# 05_LEDs.net
KiCad netlist of a schematic drawn in Altium Designer
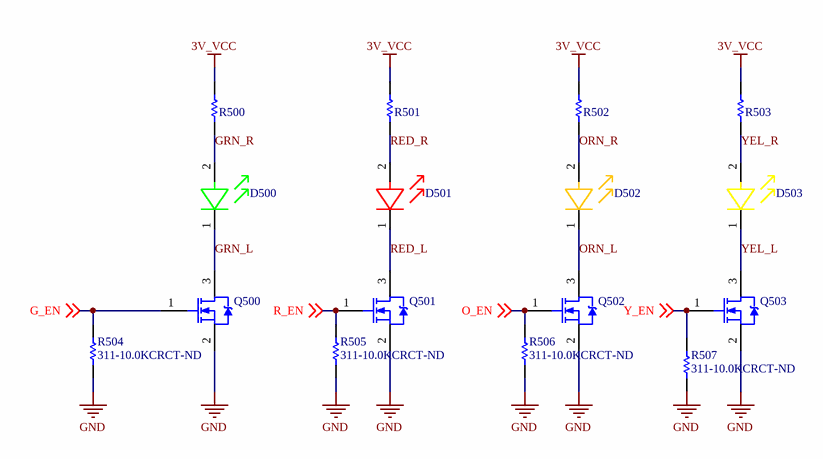
[diagram p0: 05_LEDs.SchDoc]

(export (version "E")
  (design (tool "Eeschema 10.0.6"))
  (components
    (comp (ref "D500")
      (value "LED_GREEN_0805.1")
      (footprint "LED_GRN_0805")
      (description "LED GREEN CLEAR THIN 0805 SMD")
      (fields
        (field (name "MANUFACTURER") "Vishay / Lite-On")
        (field (name "MANUFACTURER PART NUMBER") "LTST-C171KGKT")
      )
      (libsource (lib "ece315") (part "LED_GREEN_0805.1"))
    )
    (comp (ref "D501")
      (value "LED_RED_0805.1")
      (footprint "LED_RED_0805")
      (description "LED SUPER RED CLR THIN 0805 SMD")
      (fields
        (field (name "MANUFACTURER") "Vishay / Lite-On")
        (field (name "MANUFACTURER PART NUMBER") "LTST-C171KRKT")
      )
      (libsource (lib "ece315") (part "LED_RED_0805.1"))
    )
    (comp (ref "D502")
      (value "LED_ORANGE.0805.1")
      (footprint "LED_ORG_0805")
      (description "LED ORANGE DIFFUSED 0805 SMD")
      (fields (field (name "MANUFACTURER") "Rohm") (field (name "MANUFACTURER PART NUMBER") "SML-210DTT86"))
      (libsource (lib "ece315") (part "LED_ORANGE.0805.1"))
    )
    (comp (ref "D503")
      (value "LED_YELLOW_0805.1")
      (footprint "LED_YEL_0805")
      (description "LED YELLOW CLEAR THIN 0805 SMD")
      (fields
        (field (name "MANUFACTURER") "Vishay / Lite-On")
        (field (name "MANUFACTURER PART NUMBER") "LTST-C171KSKT")
      )
      (libsource (lib "ece315") (part "LED_YELLOW_0805.1"))
    )
    (comp (ref "Q500")
      (value "IC_NMOS_DMN2020LSN")
      (footprint "SOT23")
      (fields (field (name "MANUFACTURER") "Diodes") (field (name "MANUFACTURER PART NUMBER") "DMN2020LSN-7"))
      (libsource (lib "ece315") (part "IC_NMOS_DMN2020LSN"))
    )
    (comp (ref "Q501")
      (value "IC_NMOS_DMN2020LSN")
      (footprint "SOT23")
      (fields (field (name "MANUFACTURER") "Diodes") (field (name "MANUFACTURER PART NUMBER") "DMN2020LSN-7"))
      (libsource (lib "ece315") (part "IC_NMOS_DMN2020LSN"))
    )
    (comp (ref "Q502")
      (value "IC_NMOS_DMN2020LSN")
      (footprint "SOT23")
      (fields (field (name "MANUFACTURER") "Diodes") (field (name "MANUFACTURER PART NUMBER") "DMN2020LSN-7"))
      (libsource (lib "ece315") (part "IC_NMOS_DMN2020LSN"))
    )
    (comp (ref "Q503")
      (value "IC_NMOS_DMN2020LSN")
      (footprint "SOT23")
      (fields (field (name "MANUFACTURER") "Diodes") (field (name "MANUFACTURER PART NUMBER") "DMN2020LSN-7"))
      (libsource (lib "ece315") (part "IC_NMOS_DMN2020LSN"))
    )
    (comp (ref "R500")
      (value "330")
      (footprint "RES_0805")
      (description "RES SMD 330 OHM 1% 1/8W 0805")
      (fields
        (field (name "MANUFACTURER") "Yageo")
        (field (name "MANUFACTURER PART NUMBER") "RC0805FR-07330RL")
      )
      (libsource (lib "ece315") (part "RES_0805_R_330.00"))
    )
    (comp (ref "R501")
      (value "330")
      (footprint "RES_0805")
      (description "RES SMD 330 OHM 1% 1/8W 0805")
      (fields
        (field (name "MANUFACTURER") "Yageo")
        (field (name "MANUFACTURER PART NUMBER") "RC0805FR-07330RL")
      )
      (libsource (lib "ece315") (part "RES_0805_R_330.00"))
    )
    (comp (ref "R502")
      (value "330")
      (footprint "RES_0805")
      (description "RES SMD 330 OHM 1% 1/8W 0805")
      (fields
        (field (name "MANUFACTURER") "Yageo")
        (field (name "MANUFACTURER PART NUMBER") "RC0805FR-07330RL")
      )
      (libsource (lib "ece315") (part "RES_0805_R_330.00"))
    )
    (comp (ref "R503")
      (value "330")
      (footprint "RES_0805")
      (description "RES SMD 330 OHM 1% 1/8W 0805")
      (fields
        (field (name "MANUFACTURER") "Yageo")
        (field (name "MANUFACTURER PART NUMBER") "RC0805FR-07330RL")
      )
      (libsource (lib "ece315") (part "RES_0805_R_330.00"))
    )
    (comp (ref "R504")
      (value "10K")
      (footprint "RES_0805")
      (description "RES SMD 10K OHM 1% 1/8W 0805")
      (fields
        (field (name "MANUFACTURER") "Yageo")
        (field (name "MANUFACTURER PART NUMBER") "RC0805FR-0710KL")
        (field (name "SUPPLIER PART NUMBER 1") "311-10.0KCRCT-ND")
      )
      (libsource (lib "ece315") (part "RES_0805_K_010.00"))
    )
    (comp (ref "R505")
      (value "10K")
      (footprint "RES_0805")
      (description "RES SMD 10K OHM 1% 1/8W 0805")
      (fields
        (field (name "MANUFACTURER") "Yageo")
        (field (name "MANUFACTURER PART NUMBER") "RC0805FR-0710KL")
        (field (name "SUPPLIER PART NUMBER 1") "311-10.0KCRCT-ND")
      )
      (libsource (lib "ece315") (part "RES_0805_K_010.00"))
    )
    (comp (ref "R506")
      (value "10K")
      (footprint "RES_0805")
      (description "RES SMD 10K OHM 1% 1/8W 0805")
      (fields
        (field (name "MANUFACTURER") "Yageo")
        (field (name "MANUFACTURER PART NUMBER") "RC0805FR-0710KL")
        (field (name "SUPPLIER PART NUMBER 1") "311-10.0KCRCT-ND")
      )
      (libsource (lib "ece315") (part "RES_0805_K_010.00"))
    )
    (comp (ref "R507")
      (value "10K")
      (footprint "RES_0805")
      (description "RES SMD 10K OHM 1% 1/8W 0805")
      (fields
        (field (name "MANUFACTURER") "Yageo")
        (field (name "MANUFACTURER PART NUMBER") "RC0805FR-0710KL")
        (field (name "SUPPLIER PART NUMBER 1") "311-10.0KCRCT-ND")
      )
      (libsource (lib "ece315") (part "RES_0805_K_010.00"))
    )
  )
  (nets
    (net (code "1") (name "/GRN_L") (class "Default")
      (node (ref "D500") (pin "1") (pinfunction "Cathode_1") (pintype "passive"))
      (node (ref "Q500") (pin "3") (pinfunction "3_3") (pintype "passive"))
    )
    (net (code "2") (name "/GRN_R") (class "Default")
      (node (ref "D500") (pin "2") (pinfunction "Anode_2") (pintype "passive"))
      (node (ref "R500") (pin "1") (pinfunction "1_1") (pintype "passive"))
    )
    (net (code "3") (name "/ORN_L") (class "Default")
      (node (ref "D502") (pin "1") (pinfunction "Cathode_1") (pintype "passive"))
      (node (ref "Q502") (pin "3") (pinfunction "3_3") (pintype "passive"))
    )
    (net (code "4") (name "/ORN_R") (class "Default")
      (node (ref "D502") (pin "2") (pinfunction "Anode_2") (pintype "passive"))
      (node (ref "R502") (pin "1") (pinfunction "1_1") (pintype "passive"))
    )
    (net (code "5") (name "/RED_L") (class "Default")
      (node (ref "D501") (pin "1") (pinfunction "Cathode_1") (pintype "passive"))
      (node (ref "Q501") (pin "3") (pinfunction "3_3") (pintype "passive"))
    )
    (net (code "6") (name "/RED_R") (class "Default")
      (node (ref "D501") (pin "2") (pinfunction "Anode_2") (pintype "passive"))
      (node (ref "R501") (pin "1") (pinfunction "1_1") (pintype "passive"))
    )
    (net (code "7") (name "/YEL_L") (class "Default")
      (node (ref "D503") (pin "1") (pinfunction "Cathode_1") (pintype "passive"))
      (node (ref "Q503") (pin "3") (pinfunction "3_3") (pintype "passive"))
    )
    (net (code "8") (name "/YEL_R") (class "Default")
      (node (ref "D503") (pin "2") (pinfunction "Anode_2") (pintype "passive"))
      (node (ref "R503") (pin "1") (pinfunction "1_1") (pintype "passive"))
    )
    (net (code "9") (name "3V_VCC") (class "Default")
      (node (ref "R500") (pin "2") (pinfunction "2_2") (pintype "passive"))
      (node (ref "R501") (pin "2") (pinfunction "2_2") (pintype "passive"))
      (node (ref "R502") (pin "2") (pinfunction "2_2") (pintype "passive"))
      (node (ref "R503") (pin "2") (pinfunction "2_2") (pintype "passive"))
    )
    (net (code "10") (name "GND") (class "Default")
      (node (ref "Q500") (pin "2") (pinfunction "2_2") (pintype "passive"))
      (node (ref "Q501") (pin "2") (pinfunction "2_2") (pintype "passive"))
      (node (ref "Q502") (pin "2") (pinfunction "2_2") (pintype "passive"))
      (node (ref "Q503") (pin "2") (pinfunction "2_2") (pintype "passive"))
      (node (ref "R504") (pin "1") (pinfunction "1_1") (pintype "passive"))
      (node (ref "R505") (pin "1") (pinfunction "1_1") (pintype "passive"))
      (node (ref "R506") (pin "1") (pinfunction "1_1") (pintype "passive"))
      (node (ref "R507") (pin "1") (pinfunction "1_1") (pintype "passive"))
    )
    (net (code "11") (name "G_EN") (class "Default")
      (node (ref "Q500") (pin "1") (pinfunction "1_1") (pintype "passive"))
      (node (ref "R504") (pin "2") (pinfunction "2_2") (pintype "passive"))
    )
    (net (code "12") (name "O_EN") (class "Default")
      (node (ref "Q502") (pin "1") (pinfunction "1_1") (pintype "passive"))
      (node (ref "R506") (pin "2") (pinfunction "2_2") (pintype "passive"))
    )
    (net (code "13") (name "R_EN") (class "Default")
      (node (ref "Q501") (pin "1") (pinfunction "1_1") (pintype "passive"))
      (node (ref "R505") (pin "2") (pinfunction "2_2") (pintype "passive"))
    )
    (net (code "14") (name "Y_EN") (class "Default")
      (node (ref "Q503") (pin "1") (pinfunction "1_1") (pintype "passive"))
      (node (ref "R507") (pin "2") (pinfunction "2_2") (pintype "passive"))
    )
  )
)
